# AudioMega_1206_v1.net
KiCad netlist of a schematic drawn in EAGLE
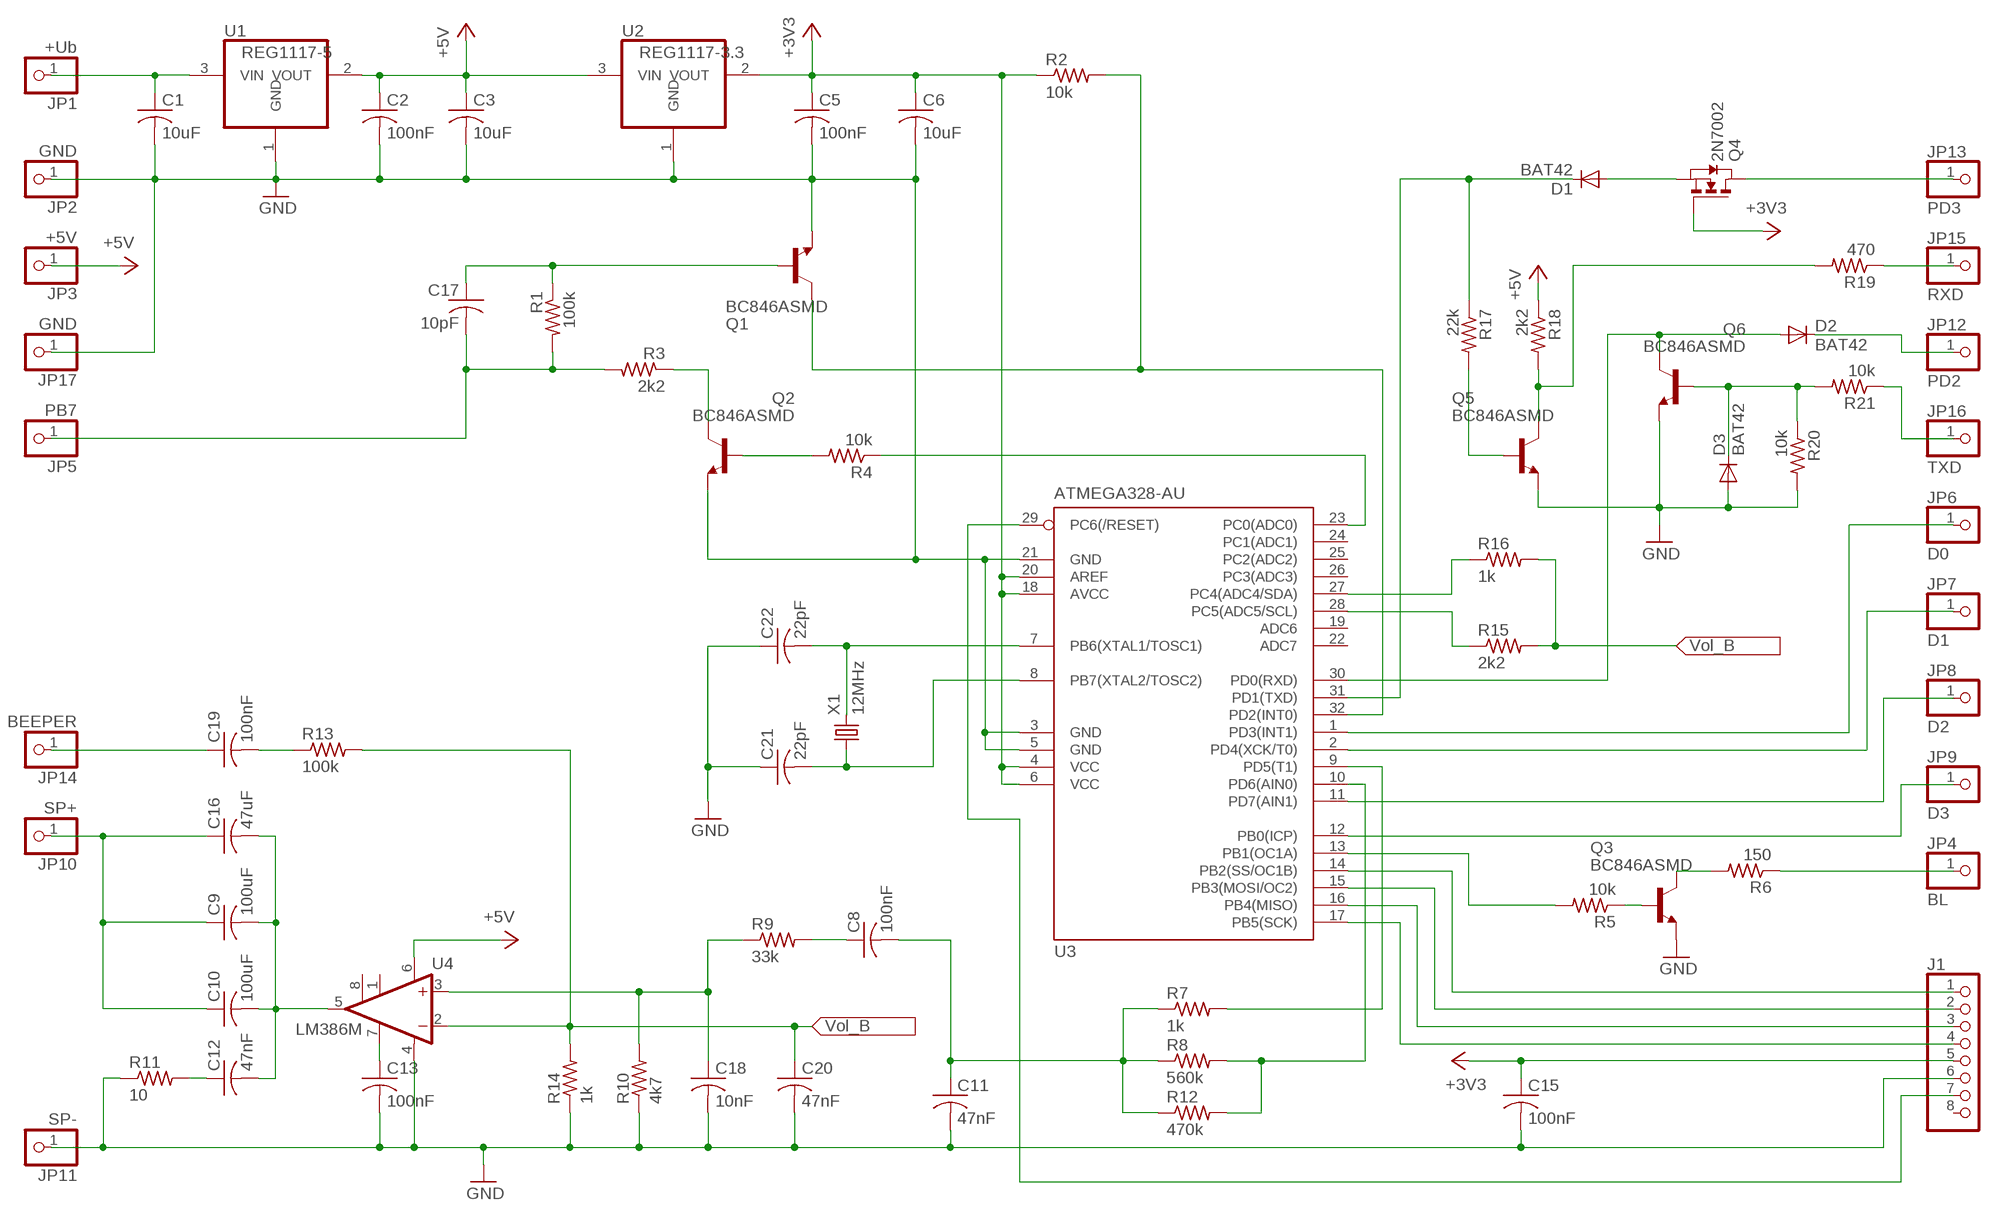
[diagram p0: schematic, sheet 1]

(export (version "E")
  (design (tool "Eeschema 10.0.6"))
  (components
    (comp (ref "C1")
      (value "10uF")
      (footprint "eagle-import:C1206")
      (libsource (lib "eagle-import") (part "C-USC1206"))
    )
    (comp (ref "C2")
      (value "100nF")
      (footprint "eagle-import:C1206")
      (libsource (lib "eagle-import") (part "C-USC1206"))
    )
    (comp (ref "C3")
      (value "10uF")
      (footprint "eagle-import:C1206")
      (libsource (lib "eagle-import") (part "C-USC1206"))
    )
    (comp (ref "C5")
      (value "100nF")
      (footprint "eagle-import:C1206")
      (libsource (lib "eagle-import") (part "C-USC1206"))
    )
    (comp (ref "C6")
      (value "10uF")
      (footprint "eagle-import:C1206")
      (libsource (lib "eagle-import") (part "C-USC1206"))
    )
    (comp (ref "C8")
      (value "100nF")
      (footprint "eagle-import:C1206")
      (libsource (lib "eagle-import") (part "C-USC1206"))
    )
    (comp (ref "C9")
      (value "100uF")
      (footprint "eagle-import:C1206")
      (libsource (lib "eagle-import") (part "C-USC1206"))
    )
    (comp (ref "C10")
      (value "100uF")
      (footprint "eagle-import:C1206")
      (libsource (lib "eagle-import") (part "C-USC1206"))
    )
    (comp (ref "C11")
      (value "47nF")
      (footprint "eagle-import:C1206")
      (libsource (lib "eagle-import") (part "C-USC1206"))
    )
    (comp (ref "C12")
      (value "47nF")
      (footprint "eagle-import:C1206")
      (libsource (lib "eagle-import") (part "C-USC1206"))
    )
    (comp (ref "C13")
      (value "100nF")
      (footprint "eagle-import:C1206")
      (libsource (lib "eagle-import") (part "C-USC1206"))
    )
    (comp (ref "C15")
      (value "100nF")
      (footprint "eagle-import:C1206")
      (libsource (lib "eagle-import") (part "C-USC1206"))
    )
    (comp (ref "C16")
      (value "47uF")
      (footprint "eagle-import:C1206")
      (libsource (lib "eagle-import") (part "C-USC1206"))
    )
    (comp (ref "C17")
      (value "10pF")
      (footprint "eagle-import:C1206")
      (libsource (lib "eagle-import") (part "C-USC1206"))
    )
    (comp (ref "C18")
      (value "10nF")
      (footprint "eagle-import:C1206")
      (libsource (lib "eagle-import") (part "C-USC1206"))
    )
    (comp (ref "C19")
      (value "100nF")
      (footprint "eagle-import:C1206")
      (libsource (lib "eagle-import") (part "C-USC1206"))
    )
    (comp (ref "C20")
      (value "47nF")
      (footprint "eagle-import:C1206")
      (libsource (lib "eagle-import") (part "C-USC1206"))
    )
    (comp (ref "C21")
      (value "22pF")
      (footprint "eagle-import:C1206")
      (libsource (lib "eagle-import") (part "C-USC1206"))
    )
    (comp (ref "C22")
      (value "22pF")
      (footprint "eagle-import:C1206")
      (libsource (lib "eagle-import") (part "C-USC1206"))
    )
    (comp (ref "D1")
      (value "BAT42")
      (footprint "eagle-import:SOD123")
      (libsource (lib "eagle-import") (part "DIODE-SOD123"))
    )
    (comp (ref "D2")
      (value "BAT42")
      (footprint "eagle-import:SOD123")
      (libsource (lib "eagle-import") (part "DIODE-SOD123"))
    )
    (comp (ref "D3")
      (value "BAT42")
      (footprint "eagle-import:SOD123")
      (libsource (lib "eagle-import") (part "DIODE-SOD123"))
    )
    (comp (ref "J1")
      (value "PINHD-1X8")
      (footprint "eagle-import:1X08")
      (libsource (lib "eagle-import") (part "PINHD-1X8"))
    )
    (comp (ref "JP1")
      (value "+Ub")
      (footprint "eagle-import:1X01")
      (libsource (lib "eagle-import") (part "PINHD-1X1"))
    )
    (comp (ref "JP2")
      (value "GND")
      (footprint "eagle-import:1X01")
      (libsource (lib "eagle-import") (part "PINHD-1X1"))
    )
    (comp (ref "JP3")
      (value "+5V")
      (footprint "eagle-import:1X01")
      (libsource (lib "eagle-import") (part "PINHD-1X1"))
    )
    (comp (ref "JP4")
      (value "BL")
      (footprint "eagle-import:1X01")
      (libsource (lib "eagle-import") (part "PINHD-1X1"))
    )
    (comp (ref "JP5")
      (value "PB7")
      (footprint "eagle-import:1X01")
      (libsource (lib "eagle-import") (part "PINHD-1X1"))
    )
    (comp (ref "JP6")
      (value "D0")
      (footprint "eagle-import:1X01")
      (libsource (lib "eagle-import") (part "PINHD-1X1"))
    )
    (comp (ref "JP7")
      (value "D1")
      (footprint "eagle-import:1X01")
      (libsource (lib "eagle-import") (part "PINHD-1X1"))
    )
    (comp (ref "JP8")
      (value "D2")
      (footprint "eagle-import:1X01")
      (libsource (lib "eagle-import") (part "PINHD-1X1"))
    )
    (comp (ref "JP9")
      (value "D3")
      (footprint "eagle-import:1X01")
      (libsource (lib "eagle-import") (part "PINHD-1X1"))
    )
    (comp (ref "JP10")
      (value "SP+")
      (footprint "eagle-import:1X01")
      (libsource (lib "eagle-import") (part "PINHD-1X1"))
    )
    (comp (ref "JP11")
      (value "SP-")
      (footprint "eagle-import:1X01")
      (libsource (lib "eagle-import") (part "PINHD-1X1"))
    )
    (comp (ref "JP12")
      (value "PD2")
      (footprint "eagle-import:1X01")
      (libsource (lib "eagle-import") (part "PINHD-1X1"))
    )
    (comp (ref "JP13")
      (value "PD3")
      (footprint "eagle-import:1X01")
      (libsource (lib "eagle-import") (part "PINHD-1X1"))
    )
    (comp (ref "JP14")
      (value "BEEPER")
      (footprint "eagle-import:1X01")
      (libsource (lib "eagle-import") (part "PINHD-1X1"))
    )
    (comp (ref "JP15")
      (value "RXD")
      (footprint "eagle-import:1X01")
      (libsource (lib "eagle-import") (part "PINHD-1X1"))
    )
    (comp (ref "JP16")
      (value "TXD")
      (footprint "eagle-import:1X01")
      (libsource (lib "eagle-import") (part "PINHD-1X1"))
    )
    (comp (ref "JP17")
      (value "GND")
      (footprint "eagle-import:1X01")
      (libsource (lib "eagle-import") (part "PINHD-1X1"))
    )
    (comp (ref "Q1")
      (value "BC846ASMD")
      (footprint "eagle-import:SOT23")
      (libsource (lib "eagle-import") (part "BC846SMDA"))
    )
    (comp (ref "Q2")
      (value "BC846ASMD")
      (footprint "eagle-import:SOT23")
      (libsource (lib "eagle-import") (part "BC846SMDA"))
    )
    (comp (ref "Q3")
      (value "BC846ASMD")
      (footprint "eagle-import:SOT23")
      (libsource (lib "eagle-import") (part "BC846SMDA"))
    )
    (comp (ref "Q4")
      (value "2N7002")
      (footprint "eagle-import:SOT-23")
      (libsource (lib "eagle-import") (part "NMOSSOT23"))
    )
    (comp (ref "Q5")
      (value "BC846ASMD")
      (footprint "eagle-import:SOT23")
      (libsource (lib "eagle-import") (part "BC846SMDA"))
    )
    (comp (ref "Q6")
      (value "BC846ASMD")
      (footprint "eagle-import:SOT23")
      (libsource (lib "eagle-import") (part "BC846SMDA"))
    )
    (comp (ref "R1")
      (value "100k")
      (footprint "eagle-import:R1206")
      (libsource (lib "eagle-import") (part "R-US_R1206"))
    )
    (comp (ref "R2")
      (value "10k")
      (footprint "eagle-import:R1206")
      (libsource (lib "eagle-import") (part "R-US_R1206"))
    )
    (comp (ref "R3")
      (value "2k2")
      (footprint "eagle-import:R1206")
      (libsource (lib "eagle-import") (part "R-US_R1206"))
    )
    (comp (ref "R4")
      (value "10k")
      (footprint "eagle-import:R1206")
      (libsource (lib "eagle-import") (part "R-US_R1206"))
    )
    (comp (ref "R5")
      (value "10k")
      (footprint "eagle-import:R1206")
      (libsource (lib "eagle-import") (part "R-US_R1206"))
    )
    (comp (ref "R6")
      (value "150")
      (footprint "eagle-import:R1206")
      (libsource (lib "eagle-import") (part "R-US_R1206"))
    )
    (comp (ref "R7")
      (value "1k")
      (footprint "eagle-import:R1206")
      (libsource (lib "eagle-import") (part "R-US_R1206"))
    )
    (comp (ref "R8")
      (value "560k")
      (footprint "eagle-import:R1206")
      (libsource (lib "eagle-import") (part "R-US_R1206"))
    )
    (comp (ref "R9")
      (value "33k")
      (footprint "eagle-import:R1206")
      (libsource (lib "eagle-import") (part "R-US_R1206"))
    )
    (comp (ref "R10")
      (value "4k7")
      (footprint "eagle-import:R1206")
      (libsource (lib "eagle-import") (part "R-US_R1206"))
    )
    (comp (ref "R11")
      (value "10")
      (footprint "eagle-import:R1206")
      (libsource (lib "eagle-import") (part "R-US_R1206"))
    )
    (comp (ref "R12")
      (value "470k")
      (footprint "eagle-import:R1206")
      (libsource (lib "eagle-import") (part "R-US_R1206"))
    )
    (comp (ref "R13")
      (value "100k")
      (footprint "eagle-import:R1206")
      (libsource (lib "eagle-import") (part "R-US_R1206"))
    )
    (comp (ref "R14")
      (value "1k")
      (footprint "eagle-import:R1206")
      (libsource (lib "eagle-import") (part "R-US_R1206"))
    )
    (comp (ref "R15")
      (value "2k2")
      (footprint "eagle-import:R1206")
      (libsource (lib "eagle-import") (part "R-US_R1206"))
    )
    (comp (ref "R16")
      (value "1k")
      (footprint "eagle-import:R1206")
      (libsource (lib "eagle-import") (part "R-US_R1206"))
    )
    (comp (ref "R17")
      (value "22k")
      (footprint "eagle-import:R1206")
      (libsource (lib "eagle-import") (part "R-US_R1206"))
    )
    (comp (ref "R18")
      (value "2k2")
      (footprint "eagle-import:R1206")
      (libsource (lib "eagle-import") (part "R-US_R1206"))
    )
    (comp (ref "R19")
      (value "470")
      (footprint "eagle-import:R1206")
      (libsource (lib "eagle-import") (part "R-US_R1206"))
    )
    (comp (ref "R20")
      (value "10k")
      (footprint "eagle-import:R1206")
      (libsource (lib "eagle-import") (part "R-US_R1206"))
    )
    (comp (ref "R21")
      (value "10k")
      (footprint "eagle-import:R1206")
      (libsource (lib "eagle-import") (part "R-US_R1206"))
    )
    (comp (ref "U1")
      (value "REG1117-5")
      (footprint "eagle-import:SOT223")
      (fields (field (name "MPN") "REG1117"))
      (libsource (lib "eagle-import") (part "REG1117"))
    )
    (comp (ref "U2")
      (value "REG1117-3.3")
      (footprint "eagle-import:SOT223")
      (fields (field (name "MPN") "REG1117"))
      (libsource (lib "eagle-import") (part "REG1117"))
    )
    (comp (ref "U3")
      (value "ATMEGA328-AU")
      (footprint "eagle-import:TQFP32-08")
      (fields (field (name "MPN") "ATMEGA8-16AU"))
      (libsource (lib "eagle-import") (part "MEGA8-AI"))
    )
    (comp (ref "U4")
      (value "LM386M")
      (footprint "eagle-import:SO08")
      (libsource (lib "eagle-import") (part "LM386?-M1"))
    )
    (comp (ref "X1")
      (value "12MHz")
      (footprint "eagle-import:HC49UP")
      (libsource (lib "eagle-import") (part "CRYSTALHC49UP"))
    )
  )
  (nets
    (net (code "1") (name "+3V3") (class "Default")
      (node (ref "C15") (pin "1") (pinfunction "1_1") (pintype "passive"))
      (node (ref "C5") (pin "1") (pinfunction "1_1") (pintype "passive"))
      (node (ref "C6") (pin "1") (pinfunction "1_1") (pintype "passive"))
      (node (ref "J1") (pin "5") (pinfunction "5_5") (pintype "passive"))
      (node (ref "Q4") (pin "3") (pinfunction "G_3") (pintype "passive"))
      (node (ref "R2") (pin "1") (pinfunction "1_1") (pintype "passive"))
      (node (ref "U2") (pin "2") (pinfunction "VOUT_2") (pintype "output"))
      (node (ref "U3") (pin "18") (pinfunction "AVCC_18") (pintype "power_in"))
      (node (ref "U3") (pin "20") (pinfunction "AREF_20") (pintype "passive"))
      (node (ref "U3") (pin "4") (pinfunction "VCC_4") (pintype "power_in"))
      (node (ref "U3") (pin "6") (pinfunction "VCC_6") (pintype "power_in"))
    )
    (net (code "2") (name "+5V") (class "Default")
      (node (ref "C2") (pin "1") (pinfunction "1_1") (pintype "passive"))
      (node (ref "C3") (pin "1") (pinfunction "1_1") (pintype "passive"))
      (node (ref "JP3") (pin "1") (pinfunction "1_1") (pintype "passive"))
      (node (ref "R18") (pin "1") (pinfunction "1_1") (pintype "passive"))
      (node (ref "U1") (pin "2") (pinfunction "VOUT_2") (pintype "output"))
      (node (ref "U2") (pin "3") (pinfunction "VIN_3") (pintype "input"))
      (node (ref "U4") (pin "6") (pinfunction "VS_6") (pintype "power_in"))
    )
    (net (code "3") (name "/VOL_B") (class "Default")
      (node (ref "C20") (pin "1") (pinfunction "1_1") (pintype "passive"))
      (node (ref "R13") (pin "2") (pinfunction "2_2") (pintype "passive"))
      (node (ref "R14") (pin "2") (pinfunction "2_2") (pintype "passive"))
      (node (ref "R15") (pin "2") (pinfunction "2_2") (pintype "passive"))
      (node (ref "R16") (pin "2") (pinfunction "2_2") (pintype "passive"))
      (node (ref "U4") (pin "2") (pinfunction "-IN_2") (pintype "input"))
    )
    (net (code "4") (name "GND") (class "Default")
      (node (ref "C1") (pin "2") (pinfunction "2_2") (pintype "passive"))
      (node (ref "C11") (pin "2") (pinfunction "2_2") (pintype "passive"))
      (node (ref "C13") (pin "2") (pinfunction "2_2") (pintype "passive"))
      (node (ref "C15") (pin "2") (pinfunction "2_2") (pintype "passive"))
      (node (ref "C18") (pin "2") (pinfunction "2_2") (pintype "passive"))
      (node (ref "C2") (pin "2") (pinfunction "2_2") (pintype "passive"))
      (node (ref "C20") (pin "2") (pinfunction "2_2") (pintype "passive"))
      (node (ref "C21") (pin "1") (pinfunction "1_1") (pintype "passive"))
      (node (ref "C22") (pin "1") (pinfunction "1_1") (pintype "passive"))
      (node (ref "C3") (pin "2") (pinfunction "2_2") (pintype "passive"))
      (node (ref "C5") (pin "2") (pinfunction "2_2") (pintype "passive"))
      (node (ref "C6") (pin "2") (pinfunction "2_2") (pintype "passive"))
      (node (ref "D3") (pin "A") (pinfunction "A_A") (pintype "passive"))
      (node (ref "J1") (pin "6") (pinfunction "6_6") (pintype "passive"))
      (node (ref "JP11") (pin "1") (pinfunction "1_1") (pintype "passive"))
      (node (ref "JP17") (pin "1") (pinfunction "1_1") (pintype "passive"))
      (node (ref "JP2") (pin "1") (pinfunction "1_1") (pintype "passive"))
      (node (ref "Q1") (pin "2") (pinfunction "E_2") (pintype "passive"))
      (node (ref "Q2") (pin "2") (pinfunction "E_2") (pintype "passive"))
      (node (ref "Q3") (pin "2") (pinfunction "E_2") (pintype "passive"))
      (node (ref "Q5") (pin "2") (pinfunction "E_2") (pintype "passive"))
      (node (ref "Q6") (pin "2") (pinfunction "E_2") (pintype "passive"))
      (node (ref "R10") (pin "1") (pinfunction "1_1") (pintype "passive"))
      (node (ref "R11") (pin "1") (pinfunction "1_1") (pintype "passive"))
      (node (ref "R14") (pin "1") (pinfunction "1_1") (pintype "passive"))
      (node (ref "R20") (pin "2") (pinfunction "2_2") (pintype "passive"))
      (node (ref "U1") (pin "1") (pinfunction "GND_1") (pintype "power_in"))
      (node (ref "U2") (pin "1") (pinfunction "GND_1") (pintype "power_in"))
      (node (ref "U3") (pin "21") (pinfunction "GND_21") (pintype "power_in"))
      (node (ref "U3") (pin "3") (pinfunction "GND_3") (pintype "power_in"))
      (node (ref "U3") (pin "5") (pinfunction "GND_5") (pintype "power_in"))
      (node (ref "U4") (pin "4") (pinfunction "GND_4") (pintype "power_in"))
    )
    (net (code "5") (name "Net-(C8-Pad1)") (class "Default")
      (node (ref "C8") (pin "1") (pinfunction "1_1") (pintype "passive"))
      (node (ref "R9") (pin "2") (pinfunction "2_2") (pintype "passive"))
    )
    (net (code "6") (name "Net-(C10-Pad1)") (class "Default")
      (node (ref "C10") (pin "1") (pinfunction "1_1") (pintype "passive"))
      (node (ref "C16") (pin "1") (pinfunction "1_1") (pintype "passive"))
      (node (ref "C9") (pin "1") (pinfunction "1_1") (pintype "passive"))
      (node (ref "JP10") (pin "1") (pinfunction "1_1") (pintype "passive"))
    )
    (net (code "7") (name "Net-(C11-Pad1)") (class "Default")
      (node (ref "C11") (pin "1") (pinfunction "1_1") (pintype "passive"))
      (node (ref "C8") (pin "2") (pinfunction "2_2") (pintype "passive"))
      (node (ref "R12") (pin "1") (pinfunction "1_1") (pintype "passive"))
      (node (ref "R7") (pin "1") (pinfunction "1_1") (pintype "passive"))
      (node (ref "R8") (pin "1") (pinfunction "1_1") (pintype "passive"))
    )
    (net (code "8") (name "Net-(C12-Pad1)") (class "Default")
      (node (ref "C12") (pin "1") (pinfunction "1_1") (pintype "passive"))
      (node (ref "R11") (pin "2") (pinfunction "2_2") (pintype "passive"))
    )
    (net (code "9") (name "Net-(C17-Pad2)") (class "Default")
      (node (ref "C17") (pin "2") (pinfunction "2_2") (pintype "passive"))
      (node (ref "JP5") (pin "1") (pinfunction "1_1") (pintype "passive"))
      (node (ref "R1") (pin "2") (pinfunction "2_2") (pintype "passive"))
      (node (ref "R3") (pin "2") (pinfunction "2_2") (pintype "passive"))
    )
    (net (code "10") (name "Net-(C19-Pad1)") (class "Default")
      (node (ref "C19") (pin "1") (pinfunction "1_1") (pintype "passive"))
      (node (ref "JP14") (pin "1") (pinfunction "1_1") (pintype "passive"))
    )
    (net (code "11") (name "Net-(C19-Pad2)") (class "Default")
      (node (ref "C19") (pin "2") (pinfunction "2_2") (pintype "passive"))
      (node (ref "R13") (pin "1") (pinfunction "1_1") (pintype "passive"))
    )
    (net (code "12") (name "Net-(D2-PadC)") (class "Default")
      (node (ref "D2") (pin "C") (pinfunction "C_C") (pintype "passive"))
      (node (ref "JP12") (pin "1") (pinfunction "1_1") (pintype "passive"))
    )
    (net (code "13") (name "Net-(JP4-Pad1)") (class "Default")
      (node (ref "JP4") (pin "1") (pinfunction "1_1") (pintype "passive"))
      (node (ref "R6") (pin "1") (pinfunction "1_1") (pintype "passive"))
    )
    (net (code "14") (name "Net-(JP15-Pad1)") (class "Default")
      (node (ref "JP15") (pin "1") (pinfunction "1_1") (pintype "passive"))
      (node (ref "R19") (pin "1") (pinfunction "1_1") (pintype "passive"))
    )
    (net (code "15") (name "Net-(JP16-Pad1)") (class "Default")
      (node (ref "JP16") (pin "1") (pinfunction "1_1") (pintype "passive"))
      (node (ref "R21") (pin "1") (pinfunction "1_1") (pintype "passive"))
    )
    (net (code "16") (name "Net-(Q1-B)") (class "Default")
      (node (ref "C17") (pin "1") (pinfunction "1_1") (pintype "passive"))
      (node (ref "Q1") (pin "1") (pinfunction "B_1") (pintype "passive"))
      (node (ref "R1") (pin "1") (pinfunction "1_1") (pintype "passive"))
    )
    (net (code "17") (name "Net-(Q1-C)") (class "Default")
      (node (ref "Q1") (pin "3") (pinfunction "C_3") (pintype "passive"))
      (node (ref "R2") (pin "2") (pinfunction "2_2") (pintype "passive"))
      (node (ref "U3") (pin "32") (pinfunction "PD2(INT0)_32") (pintype "bidirectional"))
    )
    (net (code "18") (name "Net-(Q2-B)") (class "Default")
      (node (ref "Q2") (pin "1") (pinfunction "B_1") (pintype "passive"))
      (node (ref "R4") (pin "2") (pinfunction "2_2") (pintype "passive"))
    )
    (net (code "19") (name "Net-(Q2-C)") (class "Default")
      (node (ref "Q2") (pin "3") (pinfunction "C_3") (pintype "passive"))
      (node (ref "R3") (pin "1") (pinfunction "1_1") (pintype "passive"))
    )
    (net (code "20") (name "Net-(Q3-B)") (class "Default")
      (node (ref "Q3") (pin "1") (pinfunction "B_1") (pintype "passive"))
      (node (ref "R5") (pin "1") (pinfunction "1_1") (pintype "passive"))
    )
    (net (code "21") (name "Net-(Q3-C)") (class "Default")
      (node (ref "Q3") (pin "3") (pinfunction "C_3") (pintype "passive"))
      (node (ref "R6") (pin "2") (pinfunction "2_2") (pintype "passive"))
    )
    (net (code "22") (name "Net-(Q4-D)") (class "Default")
      (node (ref "JP13") (pin "1") (pinfunction "1_1") (pintype "passive"))
      (node (ref "Q4") (pin "1") (pinfunction "D_1") (pintype "passive"))
    )
    (net (code "23") (name "Net-(Q4-S)") (class "Default")
      (node (ref "D1") (pin "A") (pinfunction "A_A") (pintype "passive"))
      (node (ref "Q4") (pin "2") (pinfunction "S_2") (pintype "passive"))
    )
    (net (code "24") (name "Net-(Q5-B)") (class "Default")
      (node (ref "Q5") (pin "1") (pinfunction "B_1") (pintype "passive"))
      (node (ref "R17") (pin "2") (pinfunction "2_2") (pintype "passive"))
    )
    (net (code "25") (name "Net-(Q5-C)") (class "Default")
      (node (ref "Q5") (pin "3") (pinfunction "C_3") (pintype "passive"))
      (node (ref "R18") (pin "2") (pinfunction "2_2") (pintype "passive"))
      (node (ref "R19") (pin "2") (pinfunction "2_2") (pintype "passive"))
    )
    (net (code "26") (name "Net-(Q6-B)") (class "Default")
      (node (ref "D3") (pin "C") (pinfunction "C_C") (pintype "passive"))
      (node (ref "Q6") (pin "1") (pinfunction "B_1") (pintype "passive"))
      (node (ref "R20") (pin "1") (pinfunction "1_1") (pintype "passive"))
      (node (ref "R21") (pin "2") (pinfunction "2_2") (pintype "passive"))
    )
    (net (code "27") (name "Net-(Q6-C)") (class "Default")
      (node (ref "D2") (pin "A") (pinfunction "A_A") (pintype "passive"))
      (node (ref "Q6") (pin "3") (pinfunction "C_3") (pintype "passive"))
      (node (ref "U3") (pin "30") (pinfunction "PD0(RXD)_30") (pintype "bidirectional"))
    )
    (net (code "28") (name "Net-(U1-VIN)") (class "Default")
      (node (ref "C1") (pin "1") (pinfunction "1_1") (pintype "passive"))
      (node (ref "JP1") (pin "1") (pinfunction "1_1") (pintype "passive"))
      (node (ref "U1") (pin "3") (pinfunction "VIN_3") (pintype "input"))
    )
    (net (code "29") (name "Net-(U3-PB0(ICP))") (class "Default")
      (node (ref "JP9") (pin "1") (pinfunction "1_1") (pintype "passive"))
      (node (ref "U3") (pin "12") (pinfunction "PB0(ICP)_12") (pintype "bidirectional"))
    )
    (net (code "30") (name "Net-(U3-PB1(OC1A))") (class "Default")
      (node (ref "R5") (pin "2") (pinfunction "2_2") (pintype "passive"))
      (node (ref "U3") (pin "13") (pinfunction "PB1(OC1A)_13") (pintype "bidirectional"))
    )
    (net (code "31") (name "Net-(U3-PB2(SS{slash}OC1B))") (class "Default")
      (node (ref "J1") (pin "1") (pinfunction "1_1") (pintype "passive"))
      (node (ref "U3") (pin "14") (pinfunction "PB2(SS/OC1B)_14") (pintype "bidirectional"))
    )
    (net (code "32") (name "Net-(U3-PB3(MOSI{slash}OC2))") (class "Default")
      (node (ref "J1") (pin "2") (pinfunction "2_2") (pintype "passive"))
      (node (ref "U3") (pin "15") (pinfunction "PB3(MOSI/OC2)_15") (pintype "bidirectional"))
    )
    (net (code "33") (name "Net-(U3-PB4(MISO))") (class "Default")
      (node (ref "J1") (pin "3") (pinfunction "3_3") (pintype "passive"))
      (node (ref "U3") (pin "16") (pinfunction "PB4(MISO)_16") (pintype "bidirectional"))
    )
    (net (code "34") (name "Net-(U3-PB5(SCK))") (class "Default")
      (node (ref "J1") (pin "4") (pinfunction "4_4") (pintype "passive"))
      (node (ref "U3") (pin "17") (pinfunction "PB5(SCK)_17") (pintype "bidirectional"))
    )
    (net (code "35") (name "Net-(U3-PB6(XTAL1{slash}TOSC1))") (class "Default")
      (node (ref "C22") (pin "2") (pinfunction "2_2") (pintype "passive"))
      (node (ref "U3") (pin "7") (pinfunction "PB6(XTAL1/TOSC1)_7") (pintype "bidirectional"))
      (node (ref "X1") (pin "2") (pinfunction "2_2") (pintype "passive"))
    )
    (net (code "36") (name "Net-(U3-PB7(XTAL2{slash}TOSC2))") (class "Default")
      (node (ref "C21") (pin "2") (pinfunction "2_2") (pintype "passive"))
      (node (ref "U3") (pin "8") (pinfunction "PB7(XTAL2/TOSC2)_8") (pintype "bidirectional"))
      (node (ref "X1") (pin "1") (pinfunction "1_1") (pintype "passive"))
    )
    (net (code "37") (name "Net-(U3-PC0(ADC0))") (class "Default")
      (node (ref "R4") (pin "1") (pinfunction "1_1") (pintype "passive"))
      (node (ref "U3") (pin "23") (pinfunction "PC0(ADC0)_23") (pintype "bidirectional"))
    )
    (net (code "38") (name "Net-(U3-PC4(ADC4{slash}SDA))") (class "Default")
      (node (ref "R16") (pin "1") (pinfunction "1_1") (pintype "passive"))
      (node (ref "U3") (pin "27") (pinfunction "PC4(ADC4/SDA)_27") (pintype "bidirectional"))
    )
    (net (code "39") (name "Net-(U3-PC5(ADC5{slash}SCL))") (class "Default")
      (node (ref "R15") (pin "1") (pinfunction "1_1") (pintype "passive"))
      (node (ref "U3") (pin "28") (pinfunction "PC5(ADC5/SCL)_28") (pintype "bidirectional"))
    )
    (net (code "40") (name "Net-(U3-PC6({slash}RESET))") (class "Default")
      (node (ref "J1") (pin "7") (pinfunction "7_7") (pintype "passive"))
      (node (ref "U3") (pin "29") (pinfunction "PC6(/RESET)_29") (pintype "bidirectional"))
    )
    (net (code "41") (name "Net-(U3-PD1(TXD))") (class "Default")
      (node (ref "D1") (pin "C") (pinfunction "C_C") (pintype "passive"))
      (node (ref "R17") (pin "1") (pinfunction "1_1") (pintype "passive"))
      (node (ref "U3") (pin "31") (pinfunction "PD1(TXD)_31") (pintype "bidirectional"))
    )
    (net (code "42") (name "Net-(U3-PD3(INT1))") (class "Default")
      (node (ref "JP6") (pin "1") (pinfunction "1_1") (pintype "passive"))
      (node (ref "U3") (pin "1") (pinfunction "PD3(INT1)_1") (pintype "bidirectional"))
    )
    (net (code "43") (name "Net-(U3-PD4(XCK{slash}T0))") (class "Default")
      (node (ref "JP7") (pin "1") (pinfunction "1_1") (pintype "passive"))
      (node (ref "U3") (pin "2") (pinfunction "PD4(XCK/T0)_2") (pintype "bidirectional"))
    )
    (net (code "44") (name "Net-(U3-PD5(T1))") (class "Default")
      (node (ref "R7") (pin "2") (pinfunction "2_2") (pintype "passive"))
      (node (ref "U3") (pin "9") (pinfunction "PD5(T1)_9") (pintype "bidirectional"))
    )
    (net (code "45") (name "Net-(U3-PD6(AIN0))") (class "Default")
      (node (ref "R12") (pin "2") (pinfunction "2_2") (pintype "passive"))
      (node (ref "R8") (pin "2") (pinfunction "2_2") (pintype "passive"))
      (node (ref "U3") (pin "10") (pinfunction "PD6(AIN0)_10") (pintype "bidirectional"))
    )
    (net (code "46") (name "Net-(U3-PD7(AIN1))") (class "Default")
      (node (ref "JP8") (pin "1") (pinfunction "1_1") (pintype "passive"))
      (node (ref "U3") (pin "11") (pinfunction "PD7(AIN1)_11") (pintype "bidirectional"))
    )
    (net (code "47") (name "Net-(U4-+IN)") (class "Default")
      (node (ref "C18") (pin "1") (pinfunction "1_1") (pintype "passive"))
      (node (ref "R10") (pin "2") (pinfunction "2_2") (pintype "passive"))
      (node (ref "R9") (pin "1") (pinfunction "1_1") (pintype "passive"))
      (node (ref "U4") (pin "3") (pinfunction "+IN_3") (pintype "input"))
    )
    (net (code "48") (name "Net-(U4-BYPASS)") (class "Default")
      (node (ref "C13") (pin "1") (pinfunction "1_1") (pintype "passive"))
      (node (ref "U4") (pin "7") (pinfunction "BYPASS_7") (pintype "passive"))
    )
    (net (code "49") (name "Net-(U4-OUT)") (class "Default")
      (node (ref "C10") (pin "2") (pinfunction "2_2") (pintype "passive"))
      (node (ref "C12") (pin "2") (pinfunction "2_2") (pintype "passive"))
      (node (ref "C16") (pin "2") (pinfunction "2_2") (pintype "passive"))
      (node (ref "C9") (pin "2") (pinfunction "2_2") (pintype "passive"))
      (node (ref "U4") (pin "5") (pinfunction "OUT_5") (pintype "output"))
    )
    (net (code "50") (name "unconnected-(J1-Pad8)") (class "Default")
      (node (ref "J1") (pin "8") (pinfunction "8_8") (pintype "passive"))
    )
    (net (code "51") (name "unconnected-(U3-ADC6-Pad19)") (class "Default")
      (node (ref "U3") (pin "19") (pinfunction "ADC6_19") (pintype "bidirectional"))
    )
    (net (code "52") (name "unconnected-(U3-ADC7-Pad22)") (class "Default")
      (node (ref "U3") (pin "22") (pinfunction "ADC7_22") (pintype "bidirectional"))
    )
    (net (code "53") (name "unconnected-(U3-PC1(ADC1)-Pad24)") (class "Default")
      (node (ref "U3") (pin "24") (pinfunction "PC1(ADC1)_24") (pintype "bidirectional"))
    )
    (net (code "54") (name "unconnected-(U3-PC2(ADC2)-Pad25)") (class "Default")
      (node (ref "U3") (pin "25") (pinfunction "PC2(ADC2)_25") (pintype "bidirectional"))
    )
    (net (code "55") (name "unconnected-(U3-PC3(ADC3)-Pad26)") (class "Default")
      (node (ref "U3") (pin "26") (pinfunction "PC3(ADC3)_26") (pintype "bidirectional"))
    )
    (net (code "56") (name "unconnected-(U4-GAIN-Pad1)") (class "Default")
      (node (ref "U4") (pin "1") (pinfunction "GAIN_1") (pintype "passive"))
    )
    (net (code "57") (name "unconnected-(U4-GAIN-Pad8)") (class "Default")
      (node (ref "U4") (pin "8") (pinfunction "GAIN_8") (pintype "passive"))
    )
  )
)
